# prostownik_2k6p.net
KiCad netlist of a schematic drawn in EAGLE
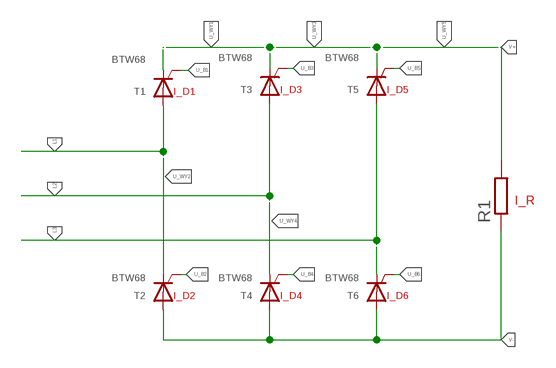
[diagram p0: schematic, sheet 1]

(export (version "E")
  (design (tool "Eeschema 10.0.6"))
  (components
    (comp (ref "R1")
      (value "R-EU_0309/12")
      (footprint "eagle-import:0309_12")
      (libsource (lib "eagle-import") (part "R-EU_0309/12"))
    )
    (comp (ref "T1")
      (value "BTW68")
      (footprint "eagle-import:TOP3S-2")
      (libsource (lib "eagle-import") (part "BTW68"))
    )
    (comp (ref "T2")
      (value "BTW68")
      (footprint "eagle-import:TOP3S-2")
      (libsource (lib "eagle-import") (part "BTW68"))
    )
    (comp (ref "T3")
      (value "BTW68")
      (footprint "eagle-import:TOP3S-2")
      (libsource (lib "eagle-import") (part "BTW68"))
    )
    (comp (ref "T4")
      (value "BTW68")
      (footprint "eagle-import:TOP3S-2")
      (libsource (lib "eagle-import") (part "BTW68"))
    )
    (comp (ref "T5")
      (value "BTW68")
      (footprint "eagle-import:TOP3S-2")
      (libsource (lib "eagle-import") (part "BTW68"))
    )
    (comp (ref "T6")
      (value "BTW68")
      (footprint "eagle-import:TOP3S-2")
      (libsource (lib "eagle-import") (part "BTW68"))
    )
  )
  (nets
    (net (code "1") (name "L1") (class "Default")
      (node (ref "T1") (pin "A") (pinfunction "A_A") (pintype "passive"))
    )
    (net (code "2") (name "L2") (class "Default")
      (node (ref "T3") (pin "A") (pinfunction "A_A") (pintype "passive"))
    )
    (net (code "3") (name "L3") (class "Default")
      (node (ref "T5") (pin "A") (pinfunction "A_A") (pintype "passive"))
    )
    (net (code "4") (name "U_B1") (class "Default")
      (node (ref "T1") (pin "G") (pinfunction "G_G") (pintype "passive"))
    )
    (net (code "5") (name "U_B2") (class "Default")
      (node (ref "T2") (pin "G") (pinfunction "G_G") (pintype "passive"))
    )
    (net (code "6") (name "U_B3") (class "Default")
      (node (ref "T3") (pin "G") (pinfunction "G_G") (pintype "passive"))
    )
    (net (code "7") (name "U_B4") (class "Default")
      (node (ref "T4") (pin "G") (pinfunction "G_G") (pintype "passive"))
    )
    (net (code "8") (name "U_B5") (class "Default")
      (node (ref "T5") (pin "G") (pinfunction "G_G") (pintype "passive"))
    )
    (net (code "9") (name "U_B6") (class "Default")
      (node (ref "T6") (pin "G") (pinfunction "G_G") (pintype "passive"))
    )
    (net (code "10") (name "U_WY1") (class "Default")
      (node (ref "T1") (pin "C") (pinfunction "C_C") (pintype "passive"))
    )
    (net (code "11") (name "U_WY2") (class "Default")
      (node (ref "T2") (pin "C") (pinfunction "C_C") (pintype "passive"))
    )
    (net (code "12") (name "U_WY3") (class "Default")
      (node (ref "T3") (pin "C") (pinfunction "C_C") (pintype "passive"))
    )
    (net (code "13") (name "U_WY4") (class "Default")
      (node (ref "T4") (pin "C") (pinfunction "C_C") (pintype "passive"))
    )
    (net (code "14") (name "U_WY5") (class "Default")
      (node (ref "T5") (pin "C") (pinfunction "C_C") (pintype "passive"))
    )
    (net (code "15") (name "V+") (class "Default")
      (node (ref "R1") (pin "2") (pinfunction "2_2") (pintype "passive"))
    )
    (net (code "16") (name "V-") (class "Default")
      (node (ref "R1") (pin "1") (pinfunction "1_1") (pintype "passive"))
      (node (ref "T2") (pin "A") (pinfunction "A_A") (pintype "passive"))
      (node (ref "T4") (pin "A") (pinfunction "A_A") (pintype "passive"))
      (node (ref "T6") (pin "A") (pinfunction "A_A") (pintype "passive"))
    )
    (net (code "17") (name "unconnected-(T6-PadC)") (class "Default")
      (node (ref "T6") (pin "C") (pinfunction "C_C") (pintype "passive"))
    )
  )
)
